# mono_stereo_mixer_noninv.net
KiCad netlist of a schematic drawn in EAGLE
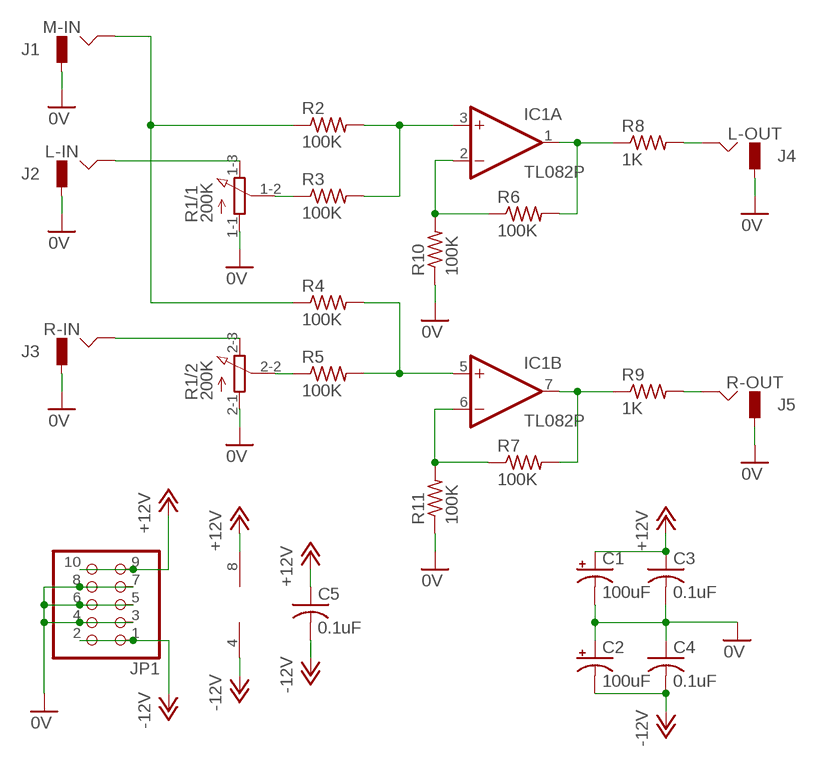
[diagram p0: schematic, sheet 1]

(export (version "E")
  (design (tool "Eeschema 10.0.6"))
  (components
    (comp (ref "C1")
      (value "100uF")
      (footprint "eagle-import:E2-5")
      (libsource (lib "eagle-import") (part "CPOL-USE2-5"))
    )
    (comp (ref "C2")
      (value "100uF")
      (footprint "eagle-import:E2-5")
      (libsource (lib "eagle-import") (part "CPOL-USE2-5"))
    )
    (comp (ref "C3")
      (value "0.1uF")
      (footprint "eagle-import:C025-024X044")
      (libsource (lib "eagle-import") (part "C-US025-024X044"))
    )
    (comp (ref "C4")
      (value "0.1uF")
      (footprint "eagle-import:C025-024X044")
      (libsource (lib "eagle-import") (part "C-US025-024X044"))
    )
    (comp (ref "C5")
      (value "0.1uF")
      (footprint "eagle-import:C025-024X044")
      (libsource (lib "eagle-import") (part "C-US025-024X044"))
    )
    (comp (ref "IC1")
      (value "TL082P")
      (footprint "eagle-import:DIL08")
      (libsource (lib "eagle-import") (part "TL082P"))
    )
    (comp (ref "J1")
      (value "M-IN")
      (footprint "eagle-import:JACK-M")
      (libsource (lib "eagle-import") (part "JACK-M"))
    )
    (comp (ref "J2")
      (value "L-IN")
      (footprint "eagle-import:JACK-M")
      (libsource (lib "eagle-import") (part "JACK-M"))
    )
    (comp (ref "J3")
      (value "R-IN")
      (footprint "eagle-import:JACK-M")
      (libsource (lib "eagle-import") (part "JACK-M"))
    )
    (comp (ref "J4")
      (value "L-OUT")
      (footprint "eagle-import:JACK-M")
      (libsource (lib "eagle-import") (part "JACK-M"))
    )
    (comp (ref "J5")
      (value "R-OUT")
      (footprint "eagle-import:JACK-M")
      (libsource (lib "eagle-import") (part "JACK-M"))
    )
    (comp (ref "JP1")
      (value "PINHD-2X5")
      (footprint "eagle-import:2X05")
      (libsource (lib "eagle-import") (part "PINHD-2X5"))
    )
    (comp (ref "R1")
      (value "200K")
      (footprint "eagle-import:3RP_1610G")
      (libsource (lib "eagle-import") (part "3RP/1610G"))
    )
    (comp (ref "R2")
      (value "100K")
      (footprint "eagle-import:0204_5")
      (libsource (lib "eagle-import") (part "R-US_0204/5"))
    )
    (comp (ref "R3")
      (value "100K")
      (footprint "eagle-import:0204_5")
      (libsource (lib "eagle-import") (part "R-US_0204/5"))
    )
    (comp (ref "R4")
      (value "100K")
      (footprint "eagle-import:0204_5")
      (libsource (lib "eagle-import") (part "R-US_0204/5"))
    )
    (comp (ref "R5")
      (value "100K")
      (footprint "eagle-import:0204_5")
      (libsource (lib "eagle-import") (part "R-US_0204/5"))
    )
    (comp (ref "R6")
      (value "100K")
      (footprint "eagle-import:0204_5")
      (libsource (lib "eagle-import") (part "R-US_0204/5"))
    )
    (comp (ref "R7")
      (value "100K")
      (footprint "eagle-import:0204_5")
      (libsource (lib "eagle-import") (part "R-US_0204/5"))
    )
    (comp (ref "R8")
      (value "1K")
      (footprint "eagle-import:0204_5")
      (libsource (lib "eagle-import") (part "R-US_0204/5"))
    )
    (comp (ref "R9")
      (value "1K")
      (footprint "eagle-import:0204_5")
      (libsource (lib "eagle-import") (part "R-US_0204/5"))
    )
    (comp (ref "R10")
      (value "100K")
      (footprint "eagle-import:0204_5")
      (libsource (lib "eagle-import") (part "R-US_0204/5"))
    )
    (comp (ref "R11")
      (value "100K")
      (footprint "eagle-import:0204_5")
      (libsource (lib "eagle-import") (part "R-US_0204/5"))
    )
  )
  (nets
    (net (code "1") (name "+12V") (class "Default")
      (node (ref "C1") (pin "+") (pinfunction "+_+") (pintype "passive"))
      (node (ref "C3") (pin "1") (pinfunction "1_1") (pintype "passive"))
      (node (ref "C5") (pin "1") (pinfunction "1_1") (pintype "passive"))
      (node (ref "IC1") (pin "8") (pinfunction "V+_8") (pintype "power_in"))
      (node (ref "JP1") (pin "10") (pinfunction "10_10") (pintype "passive"))
      (node (ref "JP1") (pin "9") (pinfunction "9_9") (pintype "passive"))
    )
    (net (code "2") (name "-12V") (class "Default")
      (node (ref "C2") (pin "-") (pinfunction "-_-") (pintype "passive"))
      (node (ref "C4") (pin "2") (pinfunction "2_2") (pintype "passive"))
      (node (ref "C5") (pin "2") (pinfunction "2_2") (pintype "passive"))
      (node (ref "IC1") (pin "4") (pinfunction "V-_4") (pintype "power_in"))
      (node (ref "JP1") (pin "1") (pinfunction "1_1") (pintype "passive"))
      (node (ref "JP1") (pin "2") (pinfunction "2_2") (pintype "passive"))
    )
    (net (code "3") (name "0V") (class "Default")
      (node (ref "C1") (pin "-") (pinfunction "-_-") (pintype "passive"))
      (node (ref "C2") (pin "+") (pinfunction "+_+") (pintype "passive"))
      (node (ref "C3") (pin "2") (pinfunction "2_2") (pintype "passive"))
      (node (ref "C4") (pin "1") (pinfunction "1_1") (pintype "passive"))
      (node (ref "J1") (pin "GND") (pinfunction "GND_GND") (pintype "bidirectional"))
      (node (ref "J2") (pin "GND") (pinfunction "GND_GND") (pintype "bidirectional"))
      (node (ref "J3") (pin "GND") (pinfunction "GND_GND") (pintype "bidirectional"))
      (node (ref "J4") (pin "GND") (pinfunction "GND_GND") (pintype "bidirectional"))
      (node (ref "J5") (pin "GND") (pinfunction "GND_GND") (pintype "bidirectional"))
      (node (ref "JP1") (pin "3") (pinfunction "3_3") (pintype "passive"))
      (node (ref "JP1") (pin "4") (pinfunction "4_4") (pintype "passive"))
      (node (ref "JP1") (pin "5") (pinfunction "5_5") (pintype "passive"))
      (node (ref "JP1") (pin "6") (pinfunction "6_6") (pintype "passive"))
      (node (ref "JP1") (pin "7") (pinfunction "7_7") (pintype "passive"))
      (node (ref "JP1") (pin "8") (pinfunction "8_8") (pintype "passive"))
      (node (ref "R1") (pin "1-1") (pinfunction "A_1-1") (pintype "passive"))
      (node (ref "R1") (pin "2-1") (pinfunction "A_2-1") (pintype "passive"))
      (node (ref "R10") (pin "1") (pinfunction "1_1") (pintype "passive"))
      (node (ref "R11") (pin "1") (pinfunction "1_1") (pintype "passive"))
    )
    (net (code "4") (name "Net-(IC1A-+IN)") (class "Default")
      (node (ref "IC1") (pin "3") (pinfunction "+IN_3") (pintype "input"))
      (node (ref "R2") (pin "2") (pinfunction "2_2") (pintype "passive"))
      (node (ref "R3") (pin "2") (pinfunction "2_2") (pintype "passive"))
    )
    (net (code "5") (name "Net-(IC1A--IN)") (class "Default")
      (node (ref "IC1") (pin "2") (pinfunction "-IN_2") (pintype "input"))
      (node (ref "R10") (pin "2") (pinfunction "2_2") (pintype "passive"))
      (node (ref "R6") (pin "1") (pinfunction "1_1") (pintype "passive"))
    )
    (net (code "6") (name "Net-(IC1A-OUT)") (class "Default")
      (node (ref "IC1") (pin "1") (pinfunction "OUT_1") (pintype "output"))
      (node (ref "R6") (pin "2") (pinfunction "2_2") (pintype "passive"))
      (node (ref "R8") (pin "1") (pinfunction "1_1") (pintype "passive"))
    )
    (net (code "7") (name "Net-(IC1B-+IN)") (class "Default")
      (node (ref "IC1") (pin "5") (pinfunction "+IN_5") (pintype "input"))
      (node (ref "R4") (pin "2") (pinfunction "2_2") (pintype "passive"))
      (node (ref "R5") (pin "2") (pinfunction "2_2") (pintype "passive"))
    )
    (net (code "8") (name "Net-(IC1B--IN)") (class "Default")
      (node (ref "IC1") (pin "6") (pinfunction "-IN_6") (pintype "input"))
      (node (ref "R11") (pin "2") (pinfunction "2_2") (pintype "passive"))
      (node (ref "R7") (pin "1") (pinfunction "1_1") (pintype "passive"))
    )
    (net (code "9") (name "Net-(IC1B-OUT)") (class "Default")
      (node (ref "IC1") (pin "7") (pinfunction "OUT_7") (pintype "output"))
      (node (ref "R7") (pin "2") (pinfunction "2_2") (pintype "passive"))
      (node (ref "R9") (pin "1") (pinfunction "1_1") (pintype "passive"))
    )
    (net (code "10") (name "Net-(J1-PadHOT)") (class "Default")
      (node (ref "J1") (pin "HOT") (pinfunction "HOT_HOT") (pintype "bidirectional"))
      (node (ref "R2") (pin "1") (pinfunction "1_1") (pintype "passive"))
      (node (ref "R4") (pin "1") (pinfunction "1_1") (pintype "passive"))
    )
    (net (code "11") (name "Net-(J4-PadHOT)") (class "Default")
      (node (ref "J4") (pin "HOT") (pinfunction "HOT_HOT") (pintype "bidirectional"))
      (node (ref "R8") (pin "2") (pinfunction "2_2") (pintype "passive"))
    )
    (net (code "12") (name "Net-(J5-PadHOT)") (class "Default")
      (node (ref "J5") (pin "HOT") (pinfunction "HOT_HOT") (pintype "bidirectional"))
      (node (ref "R9") (pin "2") (pinfunction "2_2") (pintype "passive"))
    )
    (net (code "13") (name "Net-(R1A-E)") (class "Default")
      (node (ref "J2") (pin "HOT") (pinfunction "HOT_HOT") (pintype "bidirectional"))
      (node (ref "R1") (pin "1-3") (pinfunction "E_1-3") (pintype "passive"))
    )
    (net (code "14") (name "Net-(R1A-S)") (class "Default")
      (node (ref "R1") (pin "1-2") (pinfunction "S_1-2") (pintype "passive"))
      (node (ref "R3") (pin "1") (pinfunction "1_1") (pintype "passive"))
    )
    (net (code "15") (name "Net-(R1B-E)") (class "Default")
      (node (ref "J3") (pin "HOT") (pinfunction "HOT_HOT") (pintype "bidirectional"))
      (node (ref "R1") (pin "2-3") (pinfunction "E_2-3") (pintype "passive"))
    )
    (net (code "16") (name "Net-(R1B-S)") (class "Default")
      (node (ref "R1") (pin "2-2") (pinfunction "S_2-2") (pintype "passive"))
      (node (ref "R5") (pin "1") (pinfunction "1_1") (pintype "passive"))
    )
  )
)
